# uMultimeter_ExpGPIO_Sch.net
KiCad netlist of a schematic drawn in Altium Designer
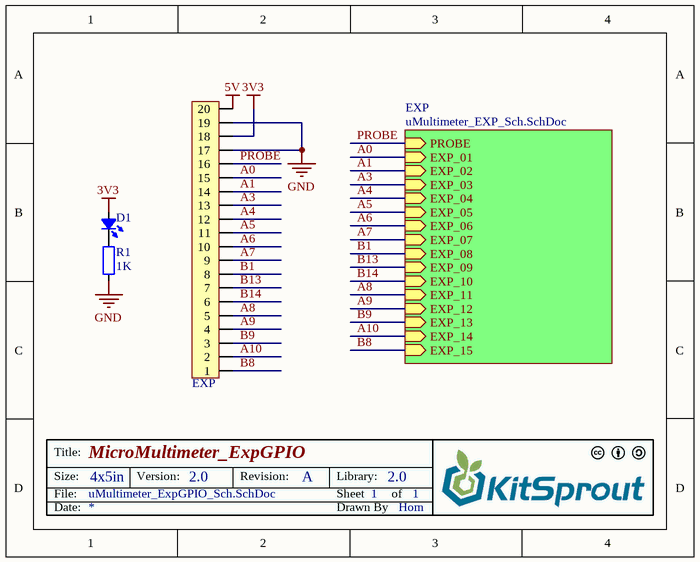
[diagram p0: uMultimeter_ExpGPIO_Sch.SchDoc]

(export (version "E")
  (design (tool "Eeschema 10.0.6"))
  (components
    (comp (ref "D1")
      (value "LED_0805")
      (footprint "PCB_ActiveLED:LED_0805_BLUE")
      (description "LED")
      (libsource (lib "SCH_Active") (part "LED_0805"))
    )
    (comp (ref "EXP")
      (value "HDR1x20_2.54")
      (footprint "PCB_ConnectorHDR:HDR1X20_2.54_180H")
      (description "Header")
      (libsource (lib "SCH_ConnectorHDR") (part "HDR1x20_2.54"))
    )
    (comp (ref "R1")
      (value "1K")
      (footprint "PCB_PassiveRes:RES_0603")
      (description "Resistor")
      (fields (field (name "Comment") "Res_0603"))
      (libsource (lib "SCH_Passive") (part "Res_0603"))
    )
  )
  (nets
    (net (code "1") (name "/A0") (class "Default")
      (node (ref "EXP") (pin "15") (pinfunction "15_15") (pintype "passive"))
    )
    (net (code "2") (name "/A1") (class "Default")
      (node (ref "EXP") (pin "14") (pinfunction "14_14") (pintype "passive"))
    )
    (net (code "3") (name "/A3") (class "Default")
      (node (ref "EXP") (pin "13") (pinfunction "13_13") (pintype "passive"))
    )
    (net (code "4") (name "/A4") (class "Default")
      (node (ref "EXP") (pin "12") (pinfunction "12_12") (pintype "passive"))
    )
    (net (code "5") (name "/A5") (class "Default")
      (node (ref "EXP") (pin "11") (pinfunction "11_11") (pintype "passive"))
    )
    (net (code "6") (name "/A6") (class "Default")
      (node (ref "EXP") (pin "10") (pinfunction "10_10") (pintype "passive"))
    )
    (net (code "7") (name "/A7") (class "Default")
      (node (ref "EXP") (pin "9") (pinfunction "9_9") (pintype "passive"))
    )
    (net (code "8") (name "/A8") (class "Default")
      (node (ref "EXP") (pin "5") (pinfunction "5_5") (pintype "passive"))
    )
    (net (code "9") (name "/A9") (class "Default")
      (node (ref "EXP") (pin "4") (pinfunction "4_4") (pintype "passive"))
    )
    (net (code "10") (name "/A10") (class "Default")
      (node (ref "EXP") (pin "2") (pinfunction "2_2") (pintype "passive"))
    )
    (net (code "11") (name "/B1") (class "Default")
      (node (ref "EXP") (pin "8") (pinfunction "8_8") (pintype "passive"))
    )
    (net (code "12") (name "/B8") (class "Default")
      (node (ref "EXP") (pin "1") (pinfunction "1_1") (pintype "passive"))
    )
    (net (code "13") (name "/B9") (class "Default")
      (node (ref "EXP") (pin "3") (pinfunction "3_3") (pintype "passive"))
    )
    (net (code "14") (name "/B13") (class "Default")
      (node (ref "EXP") (pin "7") (pinfunction "7_7") (pintype "passive"))
    )
    (net (code "15") (name "/B14") (class "Default")
      (node (ref "EXP") (pin "6") (pinfunction "6_6") (pintype "passive"))
    )
    (net (code "16") (name "/PROBE") (class "Default")
      (node (ref "EXP") (pin "16") (pinfunction "16_16") (pintype "passive"))
    )
    (net (code "17") (name "3V3") (class "Default")
      (node (ref "D1") (pin "1") (pinfunction "A_1") (pintype "passive"))
      (node (ref "EXP") (pin "18") (pinfunction "18_18") (pintype "passive"))
    )
    (net (code "18") (name "5V") (class "Default")
      (node (ref "EXP") (pin "20") (pinfunction "20_20") (pintype "passive"))
    )
    (net (code "19") (name "GND") (class "Default")
      (node (ref "EXP") (pin "17") (pinfunction "17_17") (pintype "passive"))
      (node (ref "EXP") (pin "19") (pinfunction "19_19") (pintype "passive"))
      (node (ref "R1") (pin "2") (pinfunction "2_2") (pintype "passive"))
    )
    (net (code "20") (name "Net-(D1-K)") (class "Default")
      (node (ref "D1") (pin "2") (pinfunction "K_2") (pintype "passive"))
      (node (ref "R1") (pin "1") (pinfunction "1_1") (pintype "passive"))
    )
  )
)
